# LED.net
KiCad netlist of a schematic drawn in EAGLE
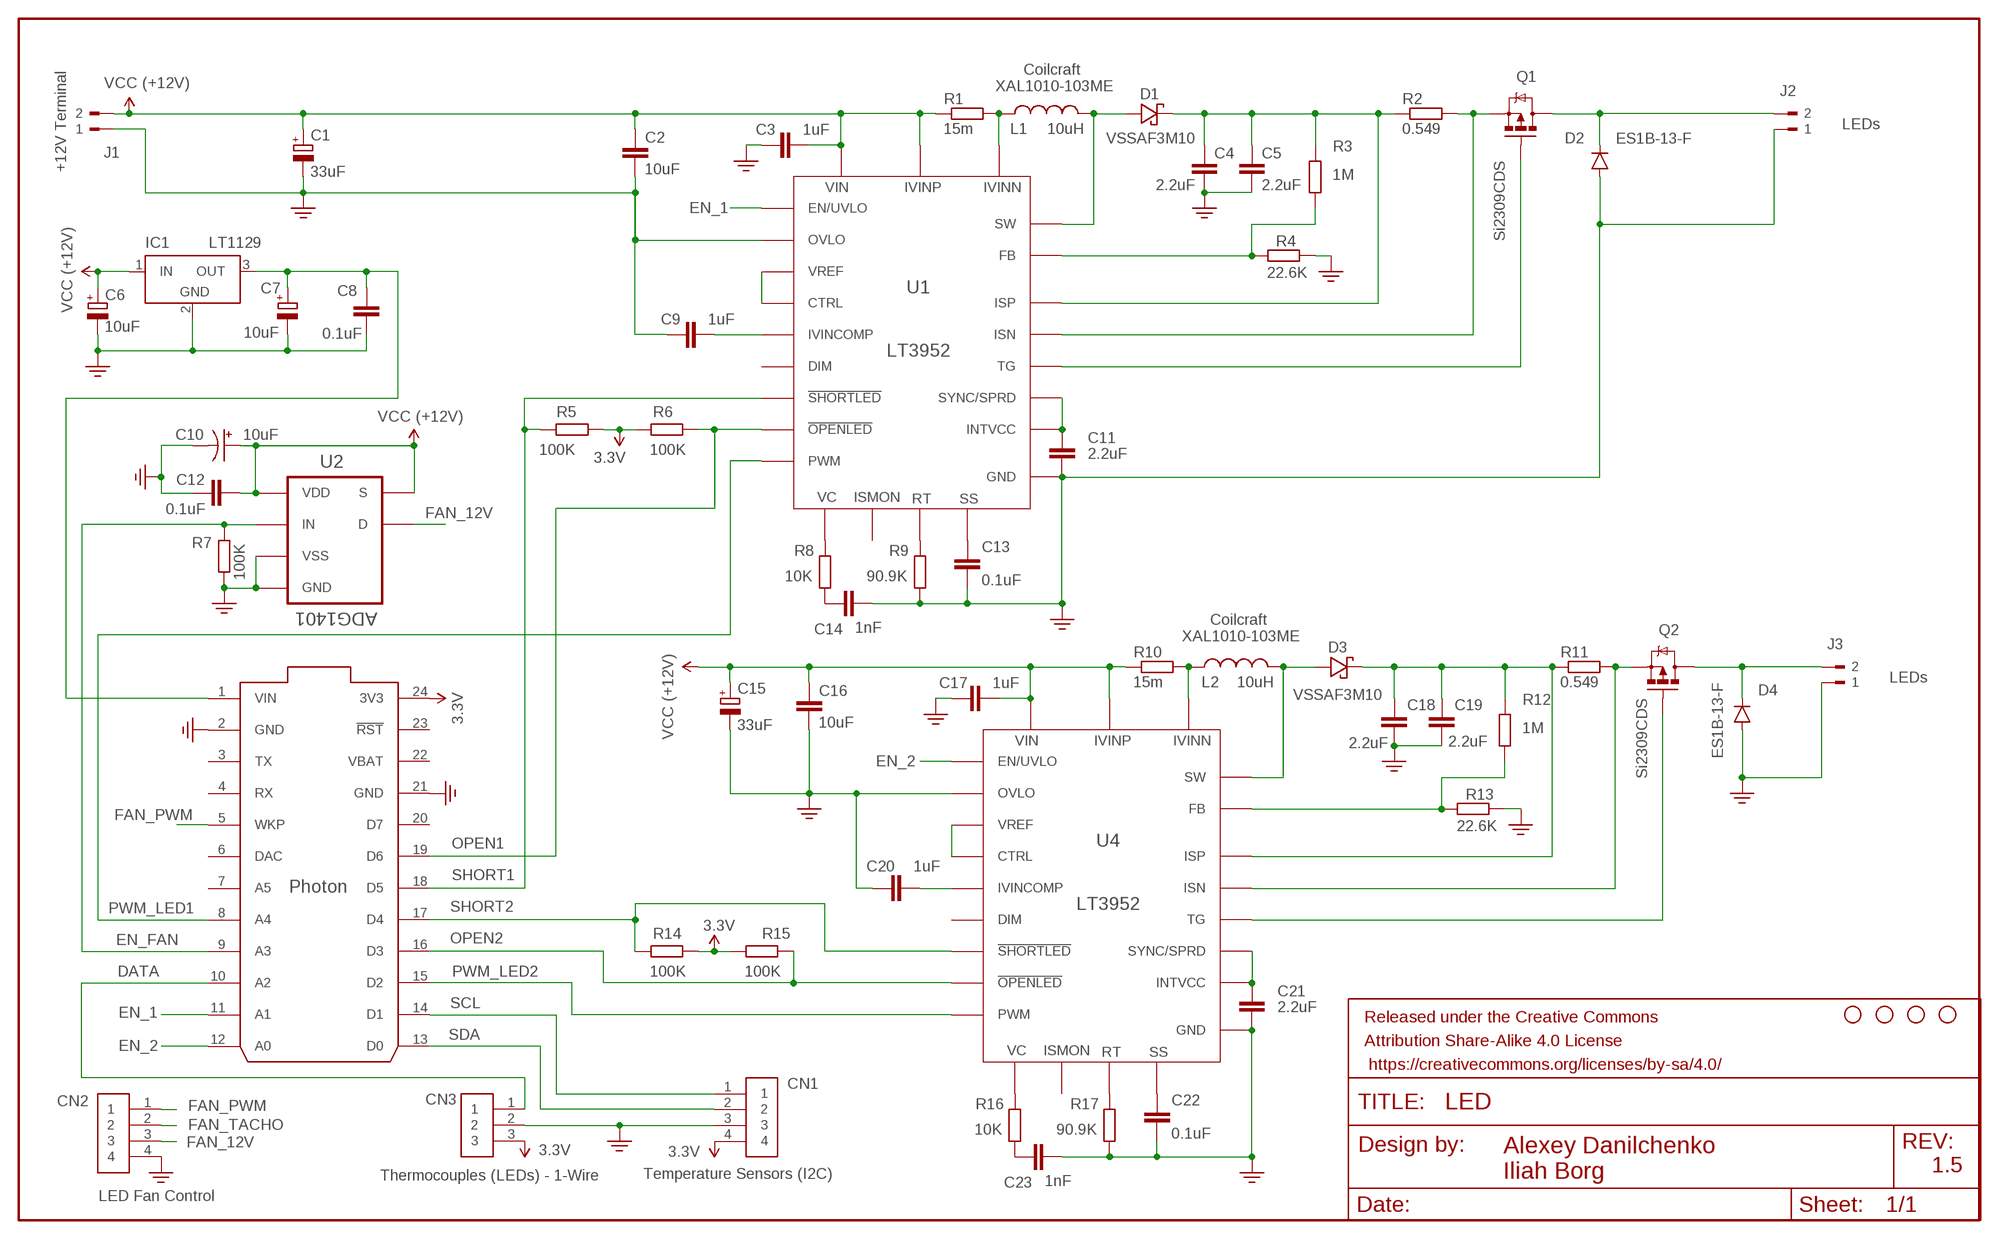
[diagram p0: schematic, sheet 1]

(export (version "E")
  (design (tool "Eeschema 10.0.6"))
  (components
    (comp (ref "C1")
      (value "33uF")
      (footprint "eagle-import:PANASONIC_E")
      (libsource (lib "eagle-import") (part "resistor_CPOL-EUE"))
    )
    (comp (ref "C2")
      (value "10uF")
      (footprint "eagle-import:C1206")
      (libsource (lib "eagle-import") (part "C-EUC1206"))
    )
    (comp (ref "C3")
      (value "1uF")
      (footprint "eagle-import:C0805")
      (libsource (lib "eagle-import") (part "rcl_C-EUC0805"))
    )
    (comp (ref "C4")
      (value "2.2uF")
      (footprint "eagle-import:C1206")
      (libsource (lib "eagle-import") (part "C-EUC1206"))
    )
    (comp (ref "C5")
      (value "2.2uF")
      (footprint "eagle-import:C1206")
      (libsource (lib "eagle-import") (part "C-EUC1206"))
    )
    (comp (ref "C6")
      (value "10uF")
      (footprint "eagle-import:CT7343")
      (libsource (lib "eagle-import") (part "CPOL-EUCT7343"))
    )
    (comp (ref "C7")
      (value "10uF")
      (footprint "eagle-import:CT7343")
      (libsource (lib "eagle-import") (part "CPOL-EUCT7343"))
    )
    (comp (ref "C8")
      (value "0.1uF")
      (footprint "eagle-import:C0805")
      (libsource (lib "eagle-import") (part "C-EUC0805"))
    )
    (comp (ref "C9")
      (value "1uF")
      (footprint "eagle-import:C0805")
      (libsource (lib "eagle-import") (part "rcl_C-EUC0805"))
    )
    (comp (ref "C10")
      (value "10uF")
      (footprint "eagle-import:EIA3216")
      (libsource (lib "eagle-import") (part "TANT-CAP1206"))
    )
    (comp (ref "C11")
      (value "2.2uF")
      (footprint "eagle-import:C0805")
      (libsource (lib "eagle-import") (part "rcl_C-EUC0805"))
    )
    (comp (ref "C12")
      (value "0.1uF")
      (footprint "eagle-import:C0805")
      (libsource (lib "eagle-import") (part "resistor_C-EUC0805"))
    )
    (comp (ref "C13")
      (value "0.1uF")
      (footprint "eagle-import:C0805")
      (libsource (lib "eagle-import") (part "rcl_C-EUC0805"))
    )
    (comp (ref "C14")
      (value "1nF")
      (footprint "eagle-import:C0805")
      (libsource (lib "eagle-import") (part "rcl_C-EUC0805"))
    )
    (comp (ref "C15")
      (value "33uF")
      (footprint "eagle-import:PANASONIC_E")
      (libsource (lib "eagle-import") (part "resistor_CPOL-EUE"))
    )
    (comp (ref "C16")
      (value "10uF")
      (footprint "eagle-import:C1206")
      (libsource (lib "eagle-import") (part "C-EUC1206"))
    )
    (comp (ref "C17")
      (value "1uF")
      (footprint "eagle-import:C0805")
      (libsource (lib "eagle-import") (part "rcl_C-EUC0805"))
    )
    (comp (ref "C18")
      (value "2.2uF")
      (footprint "eagle-import:C1206")
      (libsource (lib "eagle-import") (part "C-EUC1206"))
    )
    (comp (ref "C19")
      (value "2.2uF")
      (footprint "eagle-import:C1206")
      (libsource (lib "eagle-import") (part "C-EUC1206"))
    )
    (comp (ref "C20")
      (value "1uF")
      (footprint "eagle-import:C0805")
      (libsource (lib "eagle-import") (part "rcl_C-EUC0805"))
    )
    (comp (ref "C21")
      (value "2.2uF")
      (footprint "eagle-import:C0805")
      (libsource (lib "eagle-import") (part "rcl_C-EUC0805"))
    )
    (comp (ref "C22")
      (value "0.1uF")
      (footprint "eagle-import:C0805")
      (libsource (lib "eagle-import") (part "rcl_C-EUC0805"))
    )
    (comp (ref "C23")
      (value "1nF")
      (footprint "eagle-import:C0805")
      (libsource (lib "eagle-import") (part "rcl_C-EUC0805"))
    )
    (comp (ref "CN1")
      (value "Temperature Sensors (I2C)")
      (footprint "eagle-import:1X04-BIG")
      (libsource (lib "eagle-import") (part "1X4-BIG"))
    )
    (comp (ref "CN2")
      (value "LED Fan Control")
      (footprint "eagle-import:1X04-BIG")
      (libsource (lib "eagle-import") (part "1X4-BIG"))
    )
    (comp (ref "CN3")
      (value "Thermocouples (LEDs) - 1-Wire")
      (footprint "eagle-import:1X03")
      (libsource (lib "eagle-import") (part "1X03"))
    )
    (comp (ref "D1")
      (value "VSSAF3M10")
      (footprint "eagle-import:SODFL5226X100N")
      (fields (field (name "ARROW_PART_NUMBER") "VSSAF3M10-M3/H"))
      (libsource (lib "eagle-import") (part "VSSAF3M10-M3_H"))
    )
    (comp (ref "D2")
      (value "ES1B-13-F")
      (footprint "eagle-import:SMA-DIODE_ALT")
      (libsource (lib "eagle-import") (part "DIODESMA-ALT"))
    )
    (comp (ref "D3")
      (value "VSSAF3M10")
      (footprint "eagle-import:SODFL5226X100N")
      (fields (field (name "ARROW_PART_NUMBER") "VSSAF3M10-M3/H"))
      (libsource (lib "eagle-import") (part "VSSAF3M10-M3_H"))
    )
    (comp (ref "D4")
      (value "ES1B-13-F")
      (footprint "eagle-import:SMA-DIODE_ALT")
      (libsource (lib "eagle-import") (part "DIODESMA-ALT"))
    )
    (comp (ref "FRAME1")
      (value "1.0")
      (footprint "eagle-import:CREATIVE_COMMONS")
      (libsource (lib "eagle-import") (part "FRAME-LEDGER"))
    )
    (comp (ref "IC1")
      (value "LT1129")
      (footprint "eagle-import:SOT223")
      (libsource (lib "eagle-import") (part "LT1129CST5"))
    )
    (comp (ref "J1")
      (value "+12V Terminal")
      (footprint "eagle-import:WEIDMULLER_PM5.08_2")
      (fields (field (name "MPN") "PM5.08/2/90 BLK"))
      (libsource (lib "eagle-import") (part "PM5.08/2/90BLK"))
    )
    (comp (ref "J2")
      (value "LEDs")
      (footprint "eagle-import:WEIDMULLER_PM5.08_2")
      (fields (field (name "MPN") "PM5.08/2/90 BLK"))
      (libsource (lib "eagle-import") (part "PM5.08/2/90BLK"))
    )
    (comp (ref "J3")
      (value "LEDs")
      (footprint "eagle-import:WEIDMULLER_PM5.08_2")
      (fields (field (name "MPN") "PM5.08/2/90 BLK"))
      (libsource (lib "eagle-import") (part "PM5.08/2/90BLK"))
    )
    (comp (ref "L1")
      (value "10uH")
      (footprint "eagle-import:XAL1010")
      (libsource (lib "eagle-import") (part "XAL1010"))
    )
    (comp (ref "L2")
      (value "10uH")
      (footprint "eagle-import:XAL1010")
      (libsource (lib "eagle-import") (part "XAL1010"))
    )
    (comp (ref "Q1")
      (value "Si2309CDS")
      (footprint "eagle-import:SOT23-3")
      (libsource (lib "eagle-import") (part "MOSFET-PCHANNEL"))
    )
    (comp (ref "Q2")
      (value "Si2309CDS")
      (footprint "eagle-import:SOT23-3")
      (libsource (lib "eagle-import") (part "MOSFET-PCHANNEL"))
    )
    (comp (ref "R1")
      (value "15m")
      (footprint "eagle-import:R1206")
      (libsource (lib "eagle-import") (part "R-EU_R1206"))
    )
    (comp (ref "R2")
      (value "0.549")
      (footprint "eagle-import:R1206")
      (libsource (lib "eagle-import") (part "R-EU_R1206"))
    )
    (comp (ref "R3")
      (value "1M")
      (footprint "eagle-import:R0805")
      (libsource (lib "eagle-import") (part "R-EU_R0805"))
    )
    (comp (ref "R4")
      (value "22.6K")
      (footprint "eagle-import:R0805")
      (libsource (lib "eagle-import") (part "R-EU_R0805"))
    )
    (comp (ref "R5")
      (value "100K")
      (footprint "eagle-import:R0805")
      (libsource (lib "eagle-import") (part "R-EU_R0805"))
    )
    (comp (ref "R6")
      (value "100K")
      (footprint "eagle-import:R0805")
      (libsource (lib "eagle-import") (part "R-EU_R0805"))
    )
    (comp (ref "R7")
      (value "100K")
      (footprint "eagle-import:R0805")
      (libsource (lib "eagle-import") (part "rcl_R-EU_R0805"))
    )
    (comp (ref "R8")
      (value "10K")
      (footprint "eagle-import:R0805")
      (libsource (lib "eagle-import") (part "R-EU_R0805"))
    )
    (comp (ref "R9")
      (value "90.9K")
      (footprint "eagle-import:R0805")
      (libsource (lib "eagle-import") (part "R-EU_R0805"))
    )
    (comp (ref "R10")
      (value "15m")
      (footprint "eagle-import:R1206")
      (libsource (lib "eagle-import") (part "R-EU_R1206"))
    )
    (comp (ref "R11")
      (value "0.549")
      (footprint "eagle-import:R1206")
      (libsource (lib "eagle-import") (part "R-EU_R1206"))
    )
    (comp (ref "R12")
      (value "1M")
      (footprint "eagle-import:R0805")
      (libsource (lib "eagle-import") (part "R-EU_R0805"))
    )
    (comp (ref "R13")
      (value "22.6K")
      (footprint "eagle-import:R0805")
      (libsource (lib "eagle-import") (part "R-EU_R0805"))
    )
    (comp (ref "R14")
      (value "100K")
      (footprint "eagle-import:R0805")
      (libsource (lib "eagle-import") (part "R-EU_R0805"))
    )
    (comp (ref "R15")
      (value "100K")
      (footprint "eagle-import:R0805")
      (libsource (lib "eagle-import") (part "R-EU_R0805"))
    )
    (comp (ref "R16")
      (value "10K")
      (footprint "eagle-import:R0805")
      (libsource (lib "eagle-import") (part "R-EU_R0805"))
    )
    (comp (ref "R17")
      (value "90.9K")
      (footprint "eagle-import:R0805")
      (libsource (lib "eagle-import") (part "R-EU_R0805"))
    )
    (comp (ref "STANDOFF1")
      (value "STAND-OFF")
      (footprint "eagle-import:STAND-OFF")
      (libsource (lib "eagle-import") (part "STAND-OFF"))
    )
    (comp (ref "STANDOFF2")
      (value "STAND-OFF")
      (footprint "eagle-import:STAND-OFF")
      (libsource (lib "eagle-import") (part "STAND-OFF"))
    )
    (comp (ref "STANDOFF3")
      (value "STAND-OFF")
      (footprint "eagle-import:STAND-OFF")
      (libsource (lib "eagle-import") (part "STAND-OFF"))
    )
    (comp (ref "STANDOFF4")
      (value "STAND-OFF")
      (footprint "eagle-import:STAND-OFF")
      (libsource (lib "eagle-import") (part "STAND-OFF"))
    )
    (comp (ref "U1")
      (value "LT3952")
      (footprint "eagle-import:TSSOP-28_FE_EB-M")
      (fields (field (name "MANUFACTURER_PART_NUMBER") "LT3952EFE#PBF"))
      (libsource (lib "eagle-import") (part "LT3952EFEPBFTSSOP-28_FE/EB-M"))
    )
    (comp (ref "U2")
      (value "ADG1401")
      (footprint "eagle-import:SOP65P490X110-8N")
      (fields (field (name "MPN") "ADG1401BRMZ"))
      (libsource (lib "eagle-import") (part "ADG1401BRMZ"))
    )
    (comp (ref "U3")
      (value "PHOTON_WITH_HEADERS")
      (footprint "eagle-import:PHOTON")
      (libsource (lib "eagle-import") (part "PHOTON_WITH_HEADERS"))
    )
    (comp (ref "U4")
      (value "LT3952")
      (footprint "eagle-import:TSSOP-28_FE_EB-M")
      (fields (field (name "MANUFACTURER_PART_NUMBER") "LT3952EFE#PBF"))
      (libsource (lib "eagle-import") (part "LT3952EFEPBFTSSOP-28_FE/EB-M"))
    )
  )
  (nets
    (net (code "1") (name "/DATA") (class "Default")
      (node (ref "CN3") (pin "1") (pinfunction "1_1") (pintype "bidirectional"))
      (node (ref "U3") (pin "10") (pinfunction "A2_10") (pintype "bidirectional"))
    )
    (net (code "2") (name "/EN_1") (class "Default")
      (node (ref "U1") (pin "8") (pinfunction "EN/UVLO_8") (pintype "passive"))
      (node (ref "U3") (pin "11") (pinfunction "A1_11") (pintype "bidirectional"))
    )
    (net (code "3") (name "/EN_2") (class "Default")
      (node (ref "U3") (pin "12") (pinfunction "A0_12") (pintype "bidirectional"))
      (node (ref "U4") (pin "8") (pinfunction "EN/UVLO_8") (pintype "passive"))
    )
    (net (code "4") (name "/EN_FAN") (class "Default")
      (node (ref "R7") (pin "2") (pinfunction "2_2") (pintype "passive"))
      (node (ref "U2") (pin "6") (pinfunction "IN_6") (pintype "input"))
      (node (ref "U3") (pin "9") (pinfunction "A3_9") (pintype "bidirectional"))
    )
    (net (code "5") (name "/FAN_12V") (class "Default")
      (node (ref "CN2") (pin "3") (pinfunction "3_3") (pintype "bidirectional"))
      (node (ref "U2") (pin "8") (pinfunction "D_8") (pintype "bidirectional"))
    )
    (net (code "6") (name "/FAN_PWM") (class "Default")
      (node (ref "CN2") (pin "1") (pinfunction "1_1") (pintype "bidirectional"))
      (node (ref "U3") (pin "5") (pinfunction "WKP_5") (pintype "bidirectional"))
    )
    (net (code "7") (name "/FAN_TACHO") (class "Default")
      (node (ref "CN2") (pin "2") (pinfunction "2_2") (pintype "bidirectional"))
    )
    (net (code "8") (name "/OPEN1") (class "Default")
      (node (ref "R6") (pin "1") (pinfunction "1_1") (pintype "passive"))
      (node (ref "U1") (pin "22") (pinfunction "~{OPENLED}_22") (pintype "passive"))
      (node (ref "U3") (pin "19") (pinfunction "D6_19") (pintype "bidirectional"))
    )
    (net (code "9") (name "/OPEN2") (class "Default")
      (node (ref "R15") (pin "2") (pinfunction "2_2") (pintype "passive"))
      (node (ref "U3") (pin "16") (pinfunction "D3_16") (pintype "bidirectional"))
      (node (ref "U4") (pin "22") (pinfunction "~{OPENLED}_22") (pintype "passive"))
    )
    (net (code "10") (name "/PWM_LED1") (class "Default")
      (node (ref "U1") (pin "20") (pinfunction "PWM_20") (pintype "passive"))
      (node (ref "U3") (pin "8") (pinfunction "A4_8") (pintype "bidirectional"))
    )
    (net (code "11") (name "/PWM_LED2") (class "Default")
      (node (ref "U3") (pin "15") (pinfunction "D2_15") (pintype "bidirectional"))
      (node (ref "U4") (pin "20") (pinfunction "PWM_20") (pintype "passive"))
    )
    (net (code "12") (name "/SCL") (class "Default")
      (node (ref "CN1") (pin "1") (pinfunction "1_1") (pintype "bidirectional"))
      (node (ref "U3") (pin "14") (pinfunction "D1_14") (pintype "bidirectional"))
    )
    (net (code "13") (name "/SDA") (class "Default")
      (node (ref "CN1") (pin "2") (pinfunction "2_2") (pintype "bidirectional"))
      (node (ref "U3") (pin "13") (pinfunction "D0_13") (pintype "bidirectional"))
    )
    (net (code "14") (name "/SHORT1") (class "Default")
      (node (ref "R5") (pin "2") (pinfunction "2_2") (pintype "passive"))
      (node (ref "U1") (pin "21") (pinfunction "~{SHORTLED}_21") (pintype "passive"))
      (node (ref "U3") (pin "18") (pinfunction "D5_18") (pintype "bidirectional"))
    )
    (net (code "15") (name "/SHORT2") (class "Default")
      (node (ref "R14") (pin "1") (pinfunction "1_1") (pintype "passive"))
      (node (ref "U3") (pin "17") (pinfunction "D4_17") (pintype "bidirectional"))
      (node (ref "U4") (pin "21") (pinfunction "~{SHORTLED}_21") (pintype "passive"))
    )
    (net (code "16") (name "/VBAT") (class "Default")
      (node (ref "U3") (pin "22") (pinfunction "VBAT_22") (pintype "power_in"))
    )
    (net (code "17") (name "3.3V") (class "Default")
      (node (ref "CN1") (pin "4") (pinfunction "4_4") (pintype "bidirectional"))
      (node (ref "CN3") (pin "3") (pinfunction "3_3") (pintype "bidirectional"))
      (node (ref "R14") (pin "2") (pinfunction "2_2") (pintype "passive"))
      (node (ref "R15") (pin "1") (pinfunction "1_1") (pintype "passive"))
      (node (ref "R5") (pin "1") (pinfunction "1_1") (pintype "passive"))
      (node (ref "R6") (pin "2") (pinfunction "2_2") (pintype "passive"))
      (node (ref "U3") (pin "24") (pinfunction "3V3_24") (pintype "power_in"))
    )
    (net (code "18") (name "GND") (class "Default")
      (node (ref "C1") (pin "-") (pinfunction "-_-") (pintype "passive"))
      (node (ref "C10") (pin "C") (pinfunction "-_C") (pintype "passive"))
      (node (ref "C11") (pin "2") (pinfunction "2_2") (pintype "passive"))
      (node (ref "C12") (pin "1") (pinfunction "1_1") (pintype "passive"))
      (node (ref "C13") (pin "2") (pinfunction "2_2") (pintype "passive"))
      (node (ref "C14") (pin "2") (pinfunction "2_2") (pintype "passive"))
      (node (ref "C15") (pin "-") (pinfunction "-_-") (pintype "passive"))
      (node (ref "C16") (pin "2") (pinfunction "2_2") (pintype "passive"))
      (node (ref "C17") (pin "2") (pinfunction "2_2") (pintype "passive"))
      (node (ref "C18") (pin "2") (pinfunction "2_2") (pintype "passive"))
      (node (ref "C19") (pin "2") (pinfunction "2_2") (pintype "passive"))
      (node (ref "C2") (pin "2") (pinfunction "2_2") (pintype "passive"))
      (node (ref "C20") (pin "2") (pinfunction "2_2") (pintype "passive"))
      (node (ref "C21") (pin "2") (pinfunction "2_2") (pintype "passive"))
      (node (ref "C22") (pin "2") (pinfunction "2_2") (pintype "passive"))
      (node (ref "C23") (pin "2") (pinfunction "2_2") (pintype "passive"))
      (node (ref "C3") (pin "2") (pinfunction "2_2") (pintype "passive"))
      (node (ref "C4") (pin "2") (pinfunction "2_2") (pintype "passive"))
      (node (ref "C5") (pin "2") (pinfunction "2_2") (pintype "passive"))
      (node (ref "C6") (pin "-") (pinfunction "-_-") (pintype "passive"))
      (node (ref "C7") (pin "-") (pinfunction "-_-") (pintype "passive"))
      (node (ref "C8") (pin "2") (pinfunction "2_2") (pintype "passive"))
      (node (ref "C9") (pin "2") (pinfunction "2_2") (pintype "passive"))
      (node (ref "CN1") (pin "3") (pinfunction "3_3") (pintype "bidirectional"))
      (node (ref "CN2") (pin "4") (pinfunction "4_4") (pintype "bidirectional"))
      (node (ref "CN3") (pin "2") (pinfunction "2_2") (pintype "bidirectional"))
      (node (ref "D2") (pin "A") (pinfunction "A_A") (pintype "passive"))
      (node (ref "D4") (pin "A") (pinfunction "A_A") (pintype "passive"))
      (node (ref "IC1") (pin "2") (pinfunction "GND_2") (pintype "power_in"))
      (node (ref "J1") (pin "1") (pinfunction "1_1") (pintype "passive"))
      (node (ref "J2") (pin "1") (pinfunction "1_1") (pintype "passive"))
      (node (ref "J3") (pin "1") (pinfunction "1_1") (pintype "passive"))
      (node (ref "R13") (pin "1") (pinfunction "1_1") (pintype "passive"))
      (node (ref "R17") (pin "1") (pinfunction "1_1") (pintype "passive"))
      (node (ref "R4") (pin "1") (pinfunction "1_1") (pintype "passive"))
      (node (ref "R7") (pin "1") (pinfunction "1_1") (pintype "passive"))
      (node (ref "R9") (pin "1") (pinfunction "1_1") (pintype "passive"))
      (node (ref "U1") (pin "1") (pinfunction "GND_1") (pintype "power_in"))
      (node (ref "U1") (pin "12") (pinfunction "GND_12") (pintype "power_in"))
      (node (ref "U1") (pin "28") (pinfunction "GND_28") (pintype "power_in"))
      (node (ref "U1") (pin "9") (pinfunction "OVLO_9") (pintype "passive"))
      (node (ref "U1") (pin "EPAD") (pinfunction "GND_EPAD") (pintype "power_in"))
      (node (ref "U2") (pin "3") (pinfunction "GND_3") (pintype "passive"))
      (node (ref "U2") (pin "7") (pinfunction "VSS_7") (pintype "power_in"))
      (node (ref "U3") (pin "2") (pinfunction "GND_2") (pintype "power_in"))
      (node (ref "U3") (pin "21") (pinfunction "GND_21") (pintype "power_in"))
      (node (ref "U4") (pin "1") (pinfunction "GND_1") (pintype "power_in"))
      (node (ref "U4") (pin "12") (pinfunction "GND_12") (pintype "power_in"))
      (node (ref "U4") (pin "28") (pinfunction "GND_28") (pintype "power_in"))
      (node (ref "U4") (pin "9") (pinfunction "OVLO_9") (pintype "passive"))
      (node (ref "U4") (pin "EPAD") (pinfunction "GND_EPAD") (pintype "power_in"))
    )
    (net (code "19") (name "Net-(C14-Pad1)") (class "Default")
      (node (ref "C14") (pin "1") (pinfunction "1_1") (pintype "passive"))
      (node (ref "R8") (pin "1") (pinfunction "1_1") (pintype "passive"))
    )
    (net (code "20") (name "Net-(C23-Pad1)") (class "Default")
      (node (ref "C23") (pin "1") (pinfunction "1_1") (pintype "passive"))
      (node (ref "R16") (pin "1") (pinfunction "1_1") (pintype "passive"))
    )
    (net (code "21") (name "Net-(D1-A)") (class "Default")
      (node (ref "D1") (pin "2") (pinfunction "A_2") (pintype "bidirectional"))
      (node (ref "L1") (pin "2") (pinfunction "2_2") (pintype "passive"))
      (node (ref "U1") (pin "2") (pinfunction "SW_2") (pintype "passive"))
      (node (ref "U1") (pin "3") (pinfunction "SW_3") (pintype "passive"))
      (node (ref "U1") (pin "4") (pinfunction "SW_4") (pintype "passive"))
    )
    (net (code "22") (name "Net-(D1-K)") (class "Default")
      (node (ref "C4") (pin "1") (pinfunction "1_1") (pintype "passive"))
      (node (ref "C5") (pin "1") (pinfunction "1_1") (pintype "passive"))
      (node (ref "D1") (pin "1") (pinfunction "K_1") (pintype "bidirectional"))
      (node (ref "R2") (pin "1") (pinfunction "1_1") (pintype "passive"))
      (node (ref "R3") (pin "2") (pinfunction "2_2") (pintype "passive"))
      (node (ref "U1") (pin "27") (pinfunction "ISP_27") (pintype "output"))
    )
    (net (code "23") (name "Net-(D3-A)") (class "Default")
      (node (ref "D3") (pin "2") (pinfunction "A_2") (pintype "bidirectional"))
      (node (ref "L2") (pin "2") (pinfunction "2_2") (pintype "passive"))
      (node (ref "U4") (pin "2") (pinfunction "SW_2") (pintype "passive"))
      (node (ref "U4") (pin "3") (pinfunction "SW_3") (pintype "passive"))
      (node (ref "U4") (pin "4") (pinfunction "SW_4") (pintype "passive"))
    )
    (net (code "24") (name "Net-(D3-K)") (class "Default")
      (node (ref "C18") (pin "1") (pinfunction "1_1") (pintype "passive"))
      (node (ref "C19") (pin "1") (pinfunction "1_1") (pintype "passive"))
      (node (ref "D3") (pin "1") (pinfunction "K_1") (pintype "bidirectional"))
      (node (ref "R11") (pin "1") (pinfunction "1_1") (pintype "passive"))
      (node (ref "R12") (pin "2") (pinfunction "2_2") (pintype "passive"))
      (node (ref "U4") (pin "27") (pinfunction "ISP_27") (pintype "output"))
    )
    (net (code "25") (name "Net-(IC1A-OUT)") (class "Default")
      (node (ref "C7") (pin "+") (pinfunction "+_+") (pintype "passive"))
      (node (ref "C8") (pin "1") (pinfunction "1_1") (pintype "passive"))
      (node (ref "IC1") (pin "3") (pinfunction "OUT_3") (pintype "output"))
      (node (ref "U3") (pin "1") (pinfunction "VIN_1") (pintype "power_in"))
    )
    (net (code "26") (name "Net-(Q1-D)") (class "Default")
      (node (ref "D2") (pin "C") (pinfunction "C_C") (pintype "passive"))
      (node (ref "J2") (pin "2") (pinfunction "2_2") (pintype "passive"))
      (node (ref "Q1") (pin "3") (pinfunction "D_3") (pintype "passive"))
    )
    (net (code "27") (name "Net-(Q1-G)") (class "Default")
      (node (ref "Q1") (pin "1") (pinfunction "G_1") (pintype "passive"))
      (node (ref "U1") (pin "25") (pinfunction "TG_25") (pintype "output"))
    )
    (net (code "28") (name "Net-(Q1-S)") (class "Default")
      (node (ref "Q1") (pin "2") (pinfunction "S_2") (pintype "passive"))
      (node (ref "R2") (pin "2") (pinfunction "2_2") (pintype "passive"))
      (node (ref "U1") (pin "26") (pinfunction "ISN_26") (pintype "output"))
    )
    (net (code "29") (name "Net-(Q2-D)") (class "Default")
      (node (ref "D4") (pin "C") (pinfunction "C_C") (pintype "passive"))
      (node (ref "J3") (pin "2") (pinfunction "2_2") (pintype "passive"))
      (node (ref "Q2") (pin "3") (pinfunction "D_3") (pintype "passive"))
    )
    (net (code "30") (name "Net-(Q2-G)") (class "Default")
      (node (ref "Q2") (pin "1") (pinfunction "G_1") (pintype "passive"))
      (node (ref "U4") (pin "25") (pinfunction "TG_25") (pintype "output"))
    )
    (net (code "31") (name "Net-(Q2-S)") (class "Default")
      (node (ref "Q2") (pin "2") (pinfunction "S_2") (pintype "passive"))
      (node (ref "R11") (pin "2") (pinfunction "2_2") (pintype "passive"))
      (node (ref "U4") (pin "26") (pinfunction "ISN_26") (pintype "output"))
    )
    (net (code "32") (name "Net-(U1-CTRL)") (class "Default")
      (node (ref "U1") (pin "17") (pinfunction "CTRL_17") (pintype "output"))
      (node (ref "U1") (pin "18") (pinfunction "VREF_18") (pintype "output"))
    )
    (net (code "33") (name "Net-(U1-FB)") (class "Default")
      (node (ref "R3") (pin "1") (pinfunction "1_1") (pintype "passive"))
      (node (ref "R4") (pin "2") (pinfunction "2_2") (pintype "passive"))
      (node (ref "U1") (pin "16") (pinfunction "FB_16") (pintype "output"))
    )
    (net (code "34") (name "Net-(U1-INTVCC)") (class "Default")
      (node (ref "C11") (pin "1") (pinfunction "1_1") (pintype "passive"))
      (node (ref "U1") (pin "10") (pinfunction "INTVCC_10") (pintype "output"))
      (node (ref "U1") (pin "11") (pinfunction "SYNC/SPRD_11") (pintype "passive"))
    )
    (net (code "35") (name "Net-(U1-IVINCOMP)") (class "Default")
      (node (ref "C9") (pin "1") (pinfunction "1_1") (pintype "passive"))
      (node (ref "U1") (pin "23") (pinfunction "IVINCOMP_23") (pintype "output"))
    )
    (net (code "36") (name "Net-(U1-IVINN)") (class "Default")
      (node (ref "L1") (pin "1") (pinfunction "1_1") (pintype "passive"))
      (node (ref "R1") (pin "2") (pinfunction "2_2") (pintype "passive"))
      (node (ref "U1") (pin "5") (pinfunction "IVINN_5") (pintype "input"))
    )
    (net (code "37") (name "Net-(U1-RT)") (class "Default")
      (node (ref "R9") (pin "2") (pinfunction "2_2") (pintype "passive"))
      (node (ref "U1") (pin "14") (pinfunction "RT_14") (pintype "passive"))
    )
    (net (code "38") (name "Net-(U1-SS)") (class "Default")
      (node (ref "C13") (pin "1") (pinfunction "1_1") (pintype "passive"))
      (node (ref "U1") (pin "19") (pinfunction "SS_19") (pintype "passive"))
    )
    (net (code "39") (name "Net-(U1-VC)") (class "Default")
      (node (ref "R8") (pin "2") (pinfunction "2_2") (pintype "passive"))
      (node (ref "U1") (pin "13") (pinfunction "VC_13") (pintype "output"))
    )
    (net (code "40") (name "Net-(U4-CTRL)") (class "Default")
      (node (ref "U4") (pin "17") (pinfunction "CTRL_17") (pintype "output"))
      (node (ref "U4") (pin "18") (pinfunction "VREF_18") (pintype "output"))
    )
    (net (code "41") (name "Net-(U4-FB)") (class "Default")
      (node (ref "R12") (pin "1") (pinfunction "1_1") (pintype "passive"))
      (node (ref "R13") (pin "2") (pinfunction "2_2") (pintype "passive"))
      (node (ref "U4") (pin "16") (pinfunction "FB_16") (pintype "output"))
    )
    (net (code "42") (name "Net-(U4-INTVCC)") (class "Default")
      (node (ref "C21") (pin "1") (pinfunction "1_1") (pintype "passive"))
      (node (ref "U4") (pin "10") (pinfunction "INTVCC_10") (pintype "output"))
      (node (ref "U4") (pin "11") (pinfunction "SYNC/SPRD_11") (pintype "passive"))
    )
    (net (code "43") (name "Net-(U4-IVINCOMP)") (class "Default")
      (node (ref "C20") (pin "1") (pinfunction "1_1") (pintype "passive"))
      (node (ref "U4") (pin "23") (pinfunction "IVINCOMP_23") (pintype "output"))
    )
    (net (code "44") (name "Net-(U4-IVINN)") (class "Default")
      (node (ref "L2") (pin "1") (pinfunction "1_1") (pintype "passive"))
      (node (ref "R10") (pin "2") (pinfunction "2_2") (pintype "passive"))
      (node (ref "U4") (pin "5") (pinfunction "IVINN_5") (pintype "input"))
    )
    (net (code "45") (name "Net-(U4-RT)") (class "Default")
      (node (ref "R17") (pin "2") (pinfunction "2_2") (pintype "passive"))
      (node (ref "U4") (pin "14") (pinfunction "RT_14") (pintype "passive"))
    )
    (net (code "46") (name "Net-(U4-SS)") (class "Default")
      (node (ref "C22") (pin "1") (pinfunction "1_1") (pintype "passive"))
      (node (ref "U4") (pin "19") (pinfunction "SS_19") (pintype "passive"))
    )
    (net (code "47") (name "Net-(U4-VC)") (class "Default")
      (node (ref "R16") (pin "2") (pinfunction "2_2") (pintype "passive"))
      (node (ref "U4") (pin "13") (pinfunction "VC_13") (pintype "output"))
    )
    (net (code "48") (name "VCC (+12V)") (class "Default")
      (node (ref "C1") (pin "+") (pinfunction "+_+") (pintype "passive"))
      (node (ref "C10") (pin "A") (pinfunction "+_A") (pintype "passive"))
      (node (ref "C12") (pin "2") (pinfunction "2_2") (pintype "passive"))
      (node (ref "C15") (pin "+") (pinfunction "+_+") (pintype "passive"))
      (node (ref "C16") (pin "1") (pinfunction "1_1") (pintype "passive"))
      (node (ref "C17") (pin "1") (pinfunction "1_1") (pintype "passive"))
      (node (ref "C2") (pin "1") (pinfunction "1_1") (pintype "passive"))
      (node (ref "C3") (pin "1") (pinfunction "1_1") (pintype "passive"))
      (node (ref "C6") (pin "+") (pinfunction "+_+") (pintype "passive"))
      (node (ref "IC1") (pin "1") (pinfunction "IN_1") (pintype "input"))
      (node (ref "J1") (pin "2") (pinfunction "2_2") (pintype "passive"))
      (node (ref "R1") (pin "1") (pinfunction "1_1") (pintype "passive"))
      (node (ref "R10") (pin "1") (pinfunction "1_1") (pintype "passive"))
      (node (ref "U1") (pin "6") (pinfunction "IVINP_6") (pintype "input"))
      (node (ref "U1") (pin "7") (pinfunction "VIN_7") (pintype "input"))
      (node (ref "U2") (pin "1") (pinfunction "S_1") (pintype "bidirectional"))
      (node (ref "U2") (pin "4") (pinfunction "VDD_4") (pintype "power_in"))
      (node (ref "U4") (pin "6") (pinfunction "IVINP_6") (pintype "input"))
      (node (ref "U4") (pin "7") (pinfunction "VIN_7") (pintype "input"))
    )
    (net (code "49") (name "unconnected-(U1-DIM-Pad15)") (class "Default")
      (node (ref "U1") (pin "15") (pinfunction "DIM_15") (pintype "output"))
    )
    (net (code "50") (name "unconnected-(U1-ISMON-Pad24)") (class "Default")
      (node (ref "U1") (pin "24") (pinfunction "ISMON_24") (pintype "output"))
    )
    (net (code "51") (name "unconnected-(U3-A5-Pad7)") (class "Default")
      (node (ref "U3") (pin "7") (pinfunction "A5_7") (pintype "bidirectional"))
    )
    (net (code "52") (name "unconnected-(U3-D7-Pad20)") (class "Default")
      (node (ref "U3") (pin "20") (pinfunction "D7_20") (pintype "bidirectional"))
    )
    (net (code "53") (name "unconnected-(U3-DAC-Pad6)") (class "Default")
      (node (ref "U3") (pin "6") (pinfunction "DAC_6") (pintype "bidirectional"))
    )
    (net (code "54") (name "unconnected-(U3-RX-Pad4)") (class "Default")
      (node (ref "U3") (pin "4") (pinfunction "RX_4") (pintype "bidirectional"))
    )
    (net (code "55") (name "unconnected-(U3-TX-Pad3)") (class "Default")
      (node (ref "U3") (pin "3") (pinfunction "TX_3") (pintype "bidirectional"))
    )
    (net (code "56") (name "unconnected-(U3-~{RST}-Pad23)") (class "Default")
      (node (ref "U3") (pin "23") (pinfunction "~{RST}_23") (pintype "bidirectional"))
    )
    (net (code "57") (name "unconnected-(U4-DIM-Pad15)") (class "Default")
      (node (ref "U4") (pin "15") (pinfunction "DIM_15") (pintype "output"))
    )
    (net (code "58") (name "unconnected-(U4-ISMON-Pad24)") (class "Default")
      (node (ref "U4") (pin "24") (pinfunction "ISMON_24") (pintype "output"))
    )
  )
)
